# sch.net
KiCad netlist of a schematic drawn in EAGLE
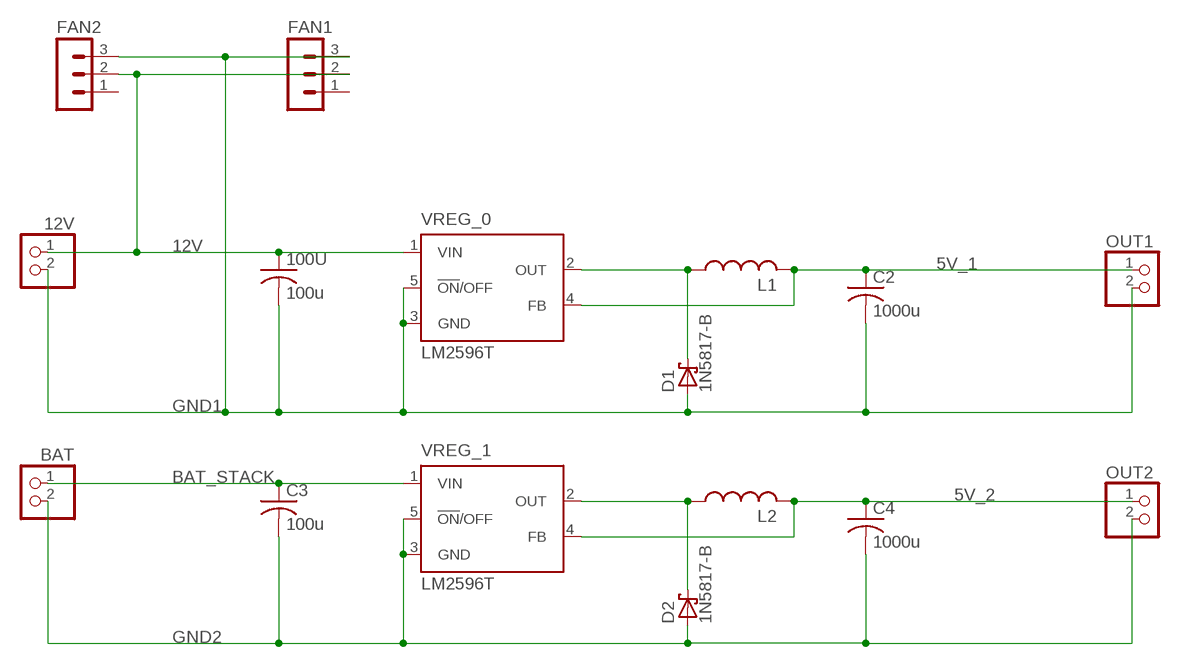
[diagram p0: schematic, sheet 1]

(export (version "E")
  (design (tool "Eeschema 10.0.6"))
  (components
    (comp (ref "12V")
      (value "PINHD-1X2")
      (footprint "eagle-import:1X02")
      (libsource (lib "eagle-import") (part "PINHD-1X2"))
    )
    (comp (ref "100U")
      (value "100u")
      (footprint "eagle-import:C025-030X050")
      (libsource (lib "eagle-import") (part "C-US025-030X050"))
    )
    (comp (ref "BAT")
      (value "PINHD-1X2")
      (footprint "eagle-import:1X02")
      (libsource (lib "eagle-import") (part "PINHD-1X2"))
    )
    (comp (ref "C2")
      (value "1000u")
      (footprint "eagle-import:C025-030X050")
      (libsource (lib "eagle-import") (part "C-US025-030X050"))
    )
    (comp (ref "C3")
      (value "100u")
      (footprint "eagle-import:C025-030X050")
      (libsource (lib "eagle-import") (part "C-US025-030X050"))
    )
    (comp (ref "C4")
      (value "1000u")
      (footprint "eagle-import:C025-030X050")
      (libsource (lib "eagle-import") (part "C-US025-030X050"))
    )
    (comp (ref "D1")
      (value "1N5817-B")
      (footprint "eagle-import:DO41-7.6")
      (libsource (lib "eagle-import") (part "1N5817-B"))
    )
    (comp (ref "D2")
      (value "1N5817-B")
      (footprint "eagle-import:DO41-7.6")
      (libsource (lib "eagle-import") (part "1N5817-B"))
    )
    (comp (ref "FAN1")
      (value "MA03-1")
      (footprint "eagle-import:MA03-1")
      (libsource (lib "eagle-import") (part "MA03-1"))
    )
    (comp (ref "FAN2")
      (value "MA03-1")
      (footprint "eagle-import:MA03-1")
      (libsource (lib "eagle-import") (part "MA03-1"))
    )
    (comp (ref "L1")
      (value "L-US6000-XXX-RC")
      (footprint "eagle-import:6000-XXXX-RC")
      (libsource (lib "eagle-import") (part "L-US6000-XXX-RC"))
    )
    (comp (ref "L2")
      (value "L-US6000-XXX-RC")
      (footprint "eagle-import:6000-XXXX-RC")
      (libsource (lib "eagle-import") (part "L-US6000-XXX-RC"))
    )
    (comp (ref "OUT1")
      (value "PINHD-1X2")
      (footprint "eagle-import:1X02")
      (libsource (lib "eagle-import") (part "PINHD-1X2"))
    )
    (comp (ref "OUT2")
      (value "PINHD-1X2")
      (footprint "eagle-import:1X02")
      (libsource (lib "eagle-import") (part "PINHD-1X2"))
    )
    (comp (ref "VREG_0")
      (value "LM2596T")
      (footprint "eagle-import:T05D")
      (fields (field (name "MPN") "LM2596T-ADJ/LF02"))
      (libsource (lib "eagle-import") (part "LM2596T"))
    )
    (comp (ref "VREG_1")
      (value "LM2596T")
      (footprint "eagle-import:T05D")
      (fields (field (name "MPN") "LM2596T-ADJ/LF02"))
      (libsource (lib "eagle-import") (part "LM2596T"))
    )
  )
  (nets
    (net (code "1") (name "/5V_1") (class "Default")
      (node (ref "C2") (pin "1") (pinfunction "1_1") (pintype "passive"))
      (node (ref "L1") (pin "2") (pinfunction "2_2") (pintype "passive"))
      (node (ref "OUT1") (pin "1") (pinfunction "1_1") (pintype "passive"))
      (node (ref "VREG_0") (pin "4") (pinfunction "FB_4") (pintype "input"))
    )
    (net (code "2") (name "/5V_2") (class "Default")
      (node (ref "C4") (pin "1") (pinfunction "1_1") (pintype "passive"))
      (node (ref "L2") (pin "2") (pinfunction "2_2") (pintype "passive"))
      (node (ref "OUT2") (pin "1") (pinfunction "1_1") (pintype "passive"))
      (node (ref "VREG_1") (pin "4") (pinfunction "FB_4") (pintype "input"))
    )
    (net (code "3") (name "/12V") (class "Default")
      (node (ref "100U") (pin "1") (pinfunction "1_1") (pintype "passive"))
      (node (ref "12V") (pin "1") (pinfunction "1_1") (pintype "passive"))
      (node (ref "FAN1") (pin "2") (pinfunction "2_2") (pintype "passive"))
      (node (ref "FAN2") (pin "2") (pinfunction "2_2") (pintype "passive"))
      (node (ref "VREG_0") (pin "1") (pinfunction "VIN_1") (pintype "input"))
    )
    (net (code "4") (name "/BAT_STACK") (class "Default")
      (node (ref "BAT") (pin "1") (pinfunction "1_1") (pintype "passive"))
      (node (ref "C3") (pin "1") (pinfunction "1_1") (pintype "passive"))
      (node (ref "VREG_1") (pin "1") (pinfunction "VIN_1") (pintype "input"))
    )
    (net (code "5") (name "/GND1") (class "Default")
      (node (ref "100U") (pin "2") (pinfunction "2_2") (pintype "passive"))
      (node (ref "12V") (pin "2") (pinfunction "2_2") (pintype "passive"))
      (node (ref "C2") (pin "2") (pinfunction "2_2") (pintype "passive"))
      (node (ref "D1") (pin "A") (pinfunction "A_A") (pintype "passive"))
      (node (ref "FAN1") (pin "3") (pinfunction "3_3") (pintype "passive"))
      (node (ref "FAN2") (pin "3") (pinfunction "3_3") (pintype "passive"))
      (node (ref "OUT1") (pin "2") (pinfunction "2_2") (pintype "passive"))
      (node (ref "VREG_0") (pin "3") (pinfunction "GND_3") (pintype "power_in"))
      (node (ref "VREG_0") (pin "5") (pinfunction "~{ON}/OFF_5") (pintype "input"))
    )
    (net (code "6") (name "/GND2") (class "Default")
      (node (ref "BAT") (pin "2") (pinfunction "2_2") (pintype "passive"))
      (node (ref "C3") (pin "2") (pinfunction "2_2") (pintype "passive"))
      (node (ref "C4") (pin "2") (pinfunction "2_2") (pintype "passive"))
      (node (ref "D2") (pin "A") (pinfunction "A_A") (pintype "passive"))
      (node (ref "OUT2") (pin "2") (pinfunction "2_2") (pintype "passive"))
      (node (ref "VREG_1") (pin "3") (pinfunction "GND_3") (pintype "power_in"))
      (node (ref "VREG_1") (pin "5") (pinfunction "~{ON}/OFF_5") (pintype "input"))
    )
    (net (code "7") (name "Net-(VREG_0-OUT)") (class "Default")
      (node (ref "D1") (pin "C") (pinfunction "C_C") (pintype "passive"))
      (node (ref "L1") (pin "1") (pinfunction "1_1") (pintype "passive"))
      (node (ref "VREG_0") (pin "2") (pinfunction "OUT_2") (pintype "output"))
    )
    (net (code "8") (name "Net-(VREG_1-OUT)") (class "Default")
      (node (ref "D2") (pin "C") (pinfunction "C_C") (pintype "passive"))
      (node (ref "L2") (pin "1") (pinfunction "1_1") (pintype "passive"))
      (node (ref "VREG_1") (pin "2") (pinfunction "OUT_2") (pintype "output"))
    )
    (net (code "9") (name "unconnected-(FAN1-Pad1)") (class "Default")
      (node (ref "FAN1") (pin "1") (pinfunction "1_1") (pintype "passive"))
    )
    (net (code "10") (name "unconnected-(FAN2-Pad1)") (class "Default")
      (node (ref "FAN2") (pin "1") (pinfunction "1_1") (pintype "passive"))
    )
  )
)
